# latch3.net
KiCad netlist of a schematic drawn in EAGLE
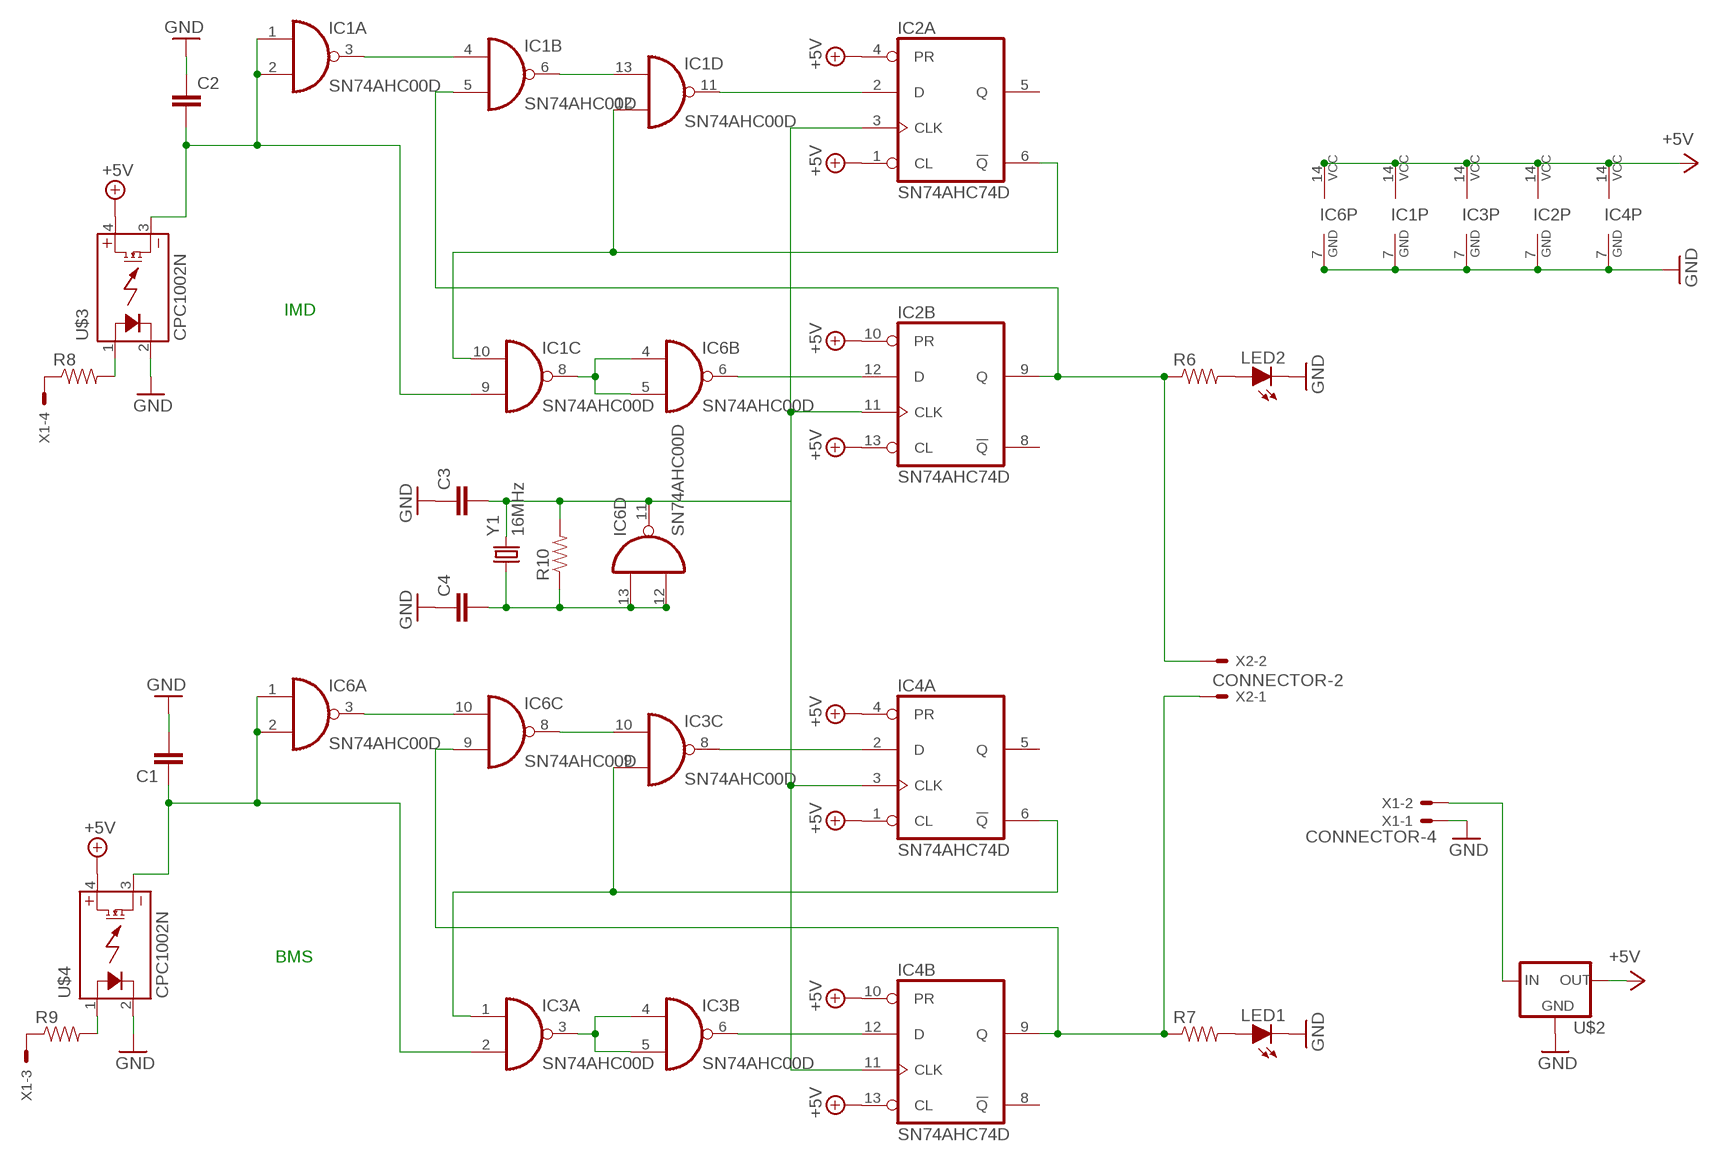
[diagram p0: schematic, sheet 1]

(export (version "E")
  (design (tool "Eeschema 10.0.6"))
  (components
    (comp (ref "C1")
      (value "CAP0402-CAP")
      (footprint "eagle-import:0402-CAP")
      (libsource (lib "eagle-import") (part "CAP0402-CAP"))
    )
    (comp (ref "C2")
      (value "CAP0402-CAP")
      (footprint "eagle-import:0402-CAP")
      (libsource (lib "eagle-import") (part "CAP0402-CAP"))
    )
    (comp (ref "C3")
      (value "CAP0402-CAP")
      (footprint "eagle-import:0402-CAP")
      (libsource (lib "eagle-import") (part "CAP0402-CAP"))
    )
    (comp (ref "C4")
      (value "CAP0402-CAP")
      (footprint "eagle-import:0402-CAP")
      (libsource (lib "eagle-import") (part "CAP0402-CAP"))
    )
    (comp (ref "IC1")
      (value "SN74AHC00D")
      (footprint "eagle-import:SOIC-14")
      (libsource (lib "eagle-import") (part "SN74AHC00D"))
    )
    (comp (ref "IC2")
      (value "SN74AHC74D")
      (footprint "eagle-import:SOIC-14")
      (libsource (lib "eagle-import") (part "SN74AHC74D"))
    )
    (comp (ref "IC3")
      (value "SN74AHC00D")
      (footprint "eagle-import:SOIC-14")
      (libsource (lib "eagle-import") (part "SN74AHC00D"))
    )
    (comp (ref "IC4")
      (value "SN74AHC74D")
      (footprint "eagle-import:SOIC-14")
      (libsource (lib "eagle-import") (part "SN74AHC74D"))
    )
    (comp (ref "IC6")
      (value "SN74AHC00D")
      (footprint "eagle-import:SOIC-14")
      (libsource (lib "eagle-import") (part "SN74AHC00D"))
    )
    (comp (ref "LED1")
      (value "LED-0805")
      (footprint "eagle-import:LED-805")
      (libsource (lib "eagle-import") (part "LED-0805"))
    )
    (comp (ref "LED2")
      (value "LED-0805")
      (footprint "eagle-import:LED-805")
      (libsource (lib "eagle-import") (part "LED-0805"))
    )
    (comp (ref "R6")
      (value "RESISTOR0402")
      (footprint "eagle-import:0402-RES")
      (libsource (lib "eagle-import") (part "RESISTOR0402"))
    )
    (comp (ref "R7")
      (value "RESISTOR0402")
      (footprint "eagle-import:0402-RES")
      (libsource (lib "eagle-import") (part "RESISTOR0402"))
    )
    (comp (ref "R8")
      (value "RESISTOR0402")
      (footprint "eagle-import:0402-RES")
      (libsource (lib "eagle-import") (part "RESISTOR0402"))
    )
    (comp (ref "R9")
      (value "RESISTOR0402")
      (footprint "eagle-import:0402-RES")
      (libsource (lib "eagle-import") (part "RESISTOR0402"))
    )
    (comp (ref "R10")
      (value "RESISTOR0402")
      (footprint "eagle-import:0402-RES")
      (libsource (lib "eagle-import") (part "RESISTOR0402"))
    )
    (comp (ref "U$2")
      (value "5VREG_LM340-NLM340MPX-5.0/NOPB")
      (footprint "eagle-import:SOT223")
      (libsource (lib "eagle-import") (part "5VREG_LM340-NLM340MPX-5.0/NOPB"))
    )
    (comp (ref "U$3")
      (value "CPC1002N")
      (footprint "eagle-import:SOP04")
      (libsource (lib "eagle-import") (part "CPC1002N"))
    )
    (comp (ref "U$4")
      (value "CPC1002N")
      (footprint "eagle-import:SOP04")
      (libsource (lib "eagle-import") (part "CPC1002N"))
    )
    (comp (ref "X1")
      (value "CONNECTOR-4")
      (footprint "eagle-import:MINIFIT_5566-4")
      (libsource (lib "eagle-import") (part "CONNECTOR-4"))
    )
    (comp (ref "X2")
      (value "CONNECTOR-2")
      (footprint "eagle-import:MINIFIT_5566-2")
      (libsource (lib "eagle-import") (part "CONNECTOR-2"))
    )
    (comp (ref "Y1")
      (value "16MHz")
      (footprint "eagle-import:CRYSTAL-SMD-3.2X1.5MM")
      (libsource (lib "eagle-import") (part "CRYSTAL3.2X1.5MM"))
    )
  )
  (nets
    (net (code "1") (name "+5V") (class "Default")
      (node (ref "IC1") (pin "14") (pinfunction "VCC_14") (pintype "power_in"))
      (node (ref "IC2") (pin "1") (pinfunction "CL_1") (pintype "input"))
      (node (ref "IC2") (pin "10") (pinfunction "PR_10") (pintype "input"))
      (node (ref "IC2") (pin "13") (pinfunction "CL_13") (pintype "input"))
      (node (ref "IC2") (pin "14") (pinfunction "VCC_14") (pintype "power_in"))
      (node (ref "IC2") (pin "4") (pinfunction "PR_4") (pintype "input"))
      (node (ref "IC3") (pin "14") (pinfunction "VCC_14") (pintype "power_in"))
      (node (ref "IC4") (pin "1") (pinfunction "CL_1") (pintype "input"))
      (node (ref "IC4") (pin "10") (pinfunction "PR_10") (pintype "input"))
      (node (ref "IC4") (pin "13") (pinfunction "CL_13") (pintype "input"))
      (node (ref "IC4") (pin "14") (pinfunction "VCC_14") (pintype "power_in"))
      (node (ref "IC4") (pin "4") (pinfunction "PR_4") (pintype "input"))
      (node (ref "IC6") (pin "14") (pinfunction "VCC_14") (pintype "power_in"))
      (node (ref "U$2") (pin "3") (pinfunction "OUT_3") (pintype "output"))
      (node (ref "U$3") (pin "4") (pinfunction "DC+_4") (pintype "passive"))
      (node (ref "U$4") (pin "4") (pinfunction "DC+_4") (pintype "passive"))
    )
    (net (code "2") (name "GND") (class "Default")
      (node (ref "C1") (pin "2") (pinfunction "2_2") (pintype "passive"))
      (node (ref "C2") (pin "1") (pinfunction "1_1") (pintype "passive"))
      (node (ref "C3") (pin "1") (pinfunction "1_1") (pintype "passive"))
      (node (ref "C4") (pin "1") (pinfunction "1_1") (pintype "passive"))
      (node (ref "IC1") (pin "7") (pinfunction "GND_7") (pintype "power_in"))
      (node (ref "IC2") (pin "7") (pinfunction "GND_7") (pintype "power_in"))
      (node (ref "IC3") (pin "7") (pinfunction "GND_7") (pintype "power_in"))
      (node (ref "IC4") (pin "7") (pinfunction "GND_7") (pintype "power_in"))
      (node (ref "IC6") (pin "7") (pinfunction "GND_7") (pintype "power_in"))
      (node (ref "LED1") (pin "C") (pinfunction "C_C") (pintype "passive"))
      (node (ref "LED2") (pin "C") (pinfunction "C_C") (pintype "passive"))
      (node (ref "U$2") (pin "2") (pinfunction "GND_2") (pintype "input"))
      (node (ref "U$2") (pin "4") (pinfunction "GND_4") (pintype "input"))
      (node (ref "U$3") (pin "2") (pinfunction "CONTROL-_2") (pintype "passive"))
      (node (ref "U$4") (pin "2") (pinfunction "CONTROL-_2") (pintype "passive"))
      (node (ref "X1") (pin "1") (pinfunction "S_1") (pintype "passive"))
    )
    (net (code "3") (name "Net-(IC1A-I0)") (class "Default")
      (node (ref "C2") (pin "2") (pinfunction "2_2") (pintype "passive"))
      (node (ref "IC1") (pin "1") (pinfunction "I0_1") (pintype "input"))
      (node (ref "IC1") (pin "2") (pinfunction "I1_2") (pintype "input"))
      (node (ref "IC1") (pin "9") (pinfunction "I1_9") (pintype "input"))
      (node (ref "U$3") (pin "3") (pinfunction "DC-_3") (pintype "passive"))
    )
    (net (code "4") (name "Net-(IC1A-O)") (class "Default")
      (node (ref "IC1") (pin "3") (pinfunction "O_3") (pintype "output"))
      (node (ref "IC1") (pin "4") (pinfunction "I0_4") (pintype "input"))
    )
    (net (code "5") (name "Net-(IC1B-I1)") (class "Default")
      (node (ref "IC1") (pin "5") (pinfunction "I1_5") (pintype "input"))
      (node (ref "IC2") (pin "9") (pinfunction "Q_9") (pintype "output"))
      (node (ref "R6") (pin "1") (pinfunction "1_1") (pintype "passive"))
      (node (ref "X2") (pin "2") (pinfunction "S_2") (pintype "passive"))
    )
    (net (code "6") (name "Net-(IC1B-O)") (class "Default")
      (node (ref "IC1") (pin "13") (pinfunction "I0_13") (pintype "input"))
      (node (ref "IC1") (pin "6") (pinfunction "O_6") (pintype "output"))
    )
    (net (code "7") (name "Net-(IC1C-I0)") (class "Default")
      (node (ref "IC1") (pin "10") (pinfunction "I0_10") (pintype "input"))
      (node (ref "IC1") (pin "12") (pinfunction "I1_12") (pintype "input"))
      (node (ref "IC2") (pin "6") (pinfunction "~{Q}_6") (pintype "output"))
    )
    (net (code "8") (name "Net-(IC1C-O)") (class "Default")
      (node (ref "IC1") (pin "8") (pinfunction "O_8") (pintype "output"))
      (node (ref "IC6") (pin "4") (pinfunction "I0_4") (pintype "input"))
      (node (ref "IC6") (pin "5") (pinfunction "I1_5") (pintype "input"))
    )
    (net (code "9") (name "Net-(IC1D-O)") (class "Default")
      (node (ref "IC1") (pin "11") (pinfunction "O_11") (pintype "output"))
      (node (ref "IC2") (pin "2") (pinfunction "D_2") (pintype "input"))
    )
    (net (code "10") (name "Net-(IC2A-CLK)") (class "Default")
      (node (ref "C3") (pin "2") (pinfunction "2_2") (pintype "passive"))
      (node (ref "IC2") (pin "11") (pinfunction "CLK_11") (pintype "input"))
      (node (ref "IC2") (pin "3") (pinfunction "CLK_3") (pintype "input"))
      (node (ref "IC4") (pin "11") (pinfunction "CLK_11") (pintype "input"))
      (node (ref "IC4") (pin "3") (pinfunction "CLK_3") (pintype "input"))
      (node (ref "IC6") (pin "11") (pinfunction "O_11") (pintype "output"))
      (node (ref "R10") (pin "2") (pinfunction "2_2") (pintype "passive"))
      (node (ref "Y1") (pin "P$2") (pinfunction "2_P$2") (pintype "passive"))
    )
    (net (code "11") (name "Net-(IC2B-D)") (class "Default")
      (node (ref "IC2") (pin "12") (pinfunction "D_12") (pintype "input"))
      (node (ref "IC6") (pin "6") (pinfunction "O_6") (pintype "output"))
    )
    (net (code "12") (name "Net-(IC3A-I0)") (class "Default")
      (node (ref "IC3") (pin "1") (pinfunction "I0_1") (pintype "input"))
      (node (ref "IC3") (pin "9") (pinfunction "I1_9") (pintype "input"))
      (node (ref "IC4") (pin "6") (pinfunction "~{Q}_6") (pintype "output"))
    )
    (net (code "13") (name "Net-(IC3A-I1)") (class "Default")
      (node (ref "C1") (pin "1") (pinfunction "1_1") (pintype "passive"))
      (node (ref "IC3") (pin "2") (pinfunction "I1_2") (pintype "input"))
      (node (ref "IC6") (pin "1") (pinfunction "I0_1") (pintype "input"))
      (node (ref "IC6") (pin "2") (pinfunction "I1_2") (pintype "input"))
      (node (ref "U$4") (pin "3") (pinfunction "DC-_3") (pintype "passive"))
    )
    (net (code "14") (name "Net-(IC3A-O)") (class "Default")
      (node (ref "IC3") (pin "3") (pinfunction "O_3") (pintype "output"))
      (node (ref "IC3") (pin "4") (pinfunction "I0_4") (pintype "input"))
      (node (ref "IC3") (pin "5") (pinfunction "I1_5") (pintype "input"))
    )
    (net (code "15") (name "Net-(IC3B-O)") (class "Default")
      (node (ref "IC3") (pin "6") (pinfunction "O_6") (pintype "output"))
      (node (ref "IC4") (pin "12") (pinfunction "D_12") (pintype "input"))
    )
    (net (code "16") (name "Net-(IC3C-I0)") (class "Default")
      (node (ref "IC3") (pin "10") (pinfunction "I0_10") (pintype "input"))
      (node (ref "IC6") (pin "8") (pinfunction "O_8") (pintype "output"))
    )
    (net (code "17") (name "Net-(IC3C-O)") (class "Default")
      (node (ref "IC3") (pin "8") (pinfunction "O_8") (pintype "output"))
      (node (ref "IC4") (pin "2") (pinfunction "D_2") (pintype "input"))
    )
    (net (code "18") (name "Net-(IC4B-Q)") (class "Default")
      (node (ref "IC4") (pin "9") (pinfunction "Q_9") (pintype "output"))
      (node (ref "IC6") (pin "9") (pinfunction "I1_9") (pintype "input"))
      (node (ref "R7") (pin "1") (pinfunction "1_1") (pintype "passive"))
      (node (ref "X2") (pin "1") (pinfunction "S_1") (pintype "passive"))
    )
    (net (code "19") (name "Net-(IC6A-O)") (class "Default")
      (node (ref "IC6") (pin "10") (pinfunction "I0_10") (pintype "input"))
      (node (ref "IC6") (pin "3") (pinfunction "O_3") (pintype "output"))
    )
    (net (code "20") (name "Net-(IC6D-I0)") (class "Default")
      (node (ref "C4") (pin "2") (pinfunction "2_2") (pintype "passive"))
      (node (ref "IC6") (pin "12") (pinfunction "I1_12") (pintype "input"))
      (node (ref "IC6") (pin "13") (pinfunction "I0_13") (pintype "input"))
      (node (ref "R10") (pin "1") (pinfunction "1_1") (pintype "passive"))
      (node (ref "Y1") (pin "P$1") (pinfunction "1_P$1") (pintype "passive"))
    )
    (net (code "21") (name "Net-(LED1-PadA)") (class "Default")
      (node (ref "LED1") (pin "A") (pinfunction "A_A") (pintype "passive"))
      (node (ref "R7") (pin "2") (pinfunction "2_2") (pintype "passive"))
    )
    (net (code "22") (name "Net-(LED2-PadA)") (class "Default")
      (node (ref "LED2") (pin "A") (pinfunction "A_A") (pintype "passive"))
      (node (ref "R6") (pin "2") (pinfunction "2_2") (pintype "passive"))
    )
    (net (code "23") (name "Net-(U$2-IN)") (class "Default")
      (node (ref "U$2") (pin "1") (pinfunction "IN_1") (pintype "input"))
      (node (ref "X1") (pin "2") (pinfunction "S_2") (pintype "passive"))
    )
    (net (code "24") (name "Net-(U$3-CONTROL+)") (class "Default")
      (node (ref "R8") (pin "2") (pinfunction "2_2") (pintype "passive"))
      (node (ref "U$3") (pin "1") (pinfunction "CONTROL+_1") (pintype "passive"))
    )
    (net (code "25") (name "Net-(U$4-CONTROL+)") (class "Default")
      (node (ref "R9") (pin "2") (pinfunction "2_2") (pintype "passive"))
      (node (ref "U$4") (pin "1") (pinfunction "CONTROL+_1") (pintype "passive"))
    )
    (net (code "26") (name "Net-(X1C-S)") (class "Default")
      (node (ref "R9") (pin "1") (pinfunction "1_1") (pintype "passive"))
      (node (ref "X1") (pin "3") (pinfunction "S_3") (pintype "passive"))
    )
    (net (code "27") (name "Net-(X1D-S)") (class "Default")
      (node (ref "R8") (pin "1") (pinfunction "1_1") (pintype "passive"))
      (node (ref "X1") (pin "4") (pinfunction "S_4") (pintype "passive"))
    )
    (net (code "28") (name "unconnected-(IC2A-Q-Pad5)") (class "Default")
      (node (ref "IC2") (pin "5") (pinfunction "Q_5") (pintype "output"))
    )
    (net (code "29") (name "unconnected-(IC2B-~{Q}-Pad8)") (class "Default")
      (node (ref "IC2") (pin "8") (pinfunction "~{Q}_8") (pintype "output"))
    )
    (net (code "30") (name "unconnected-(IC4A-Q-Pad5)") (class "Default")
      (node (ref "IC4") (pin "5") (pinfunction "Q_5") (pintype "output"))
    )
    (net (code "31") (name "unconnected-(IC4B-~{Q}-Pad8)") (class "Default")
      (node (ref "IC4") (pin "8") (pinfunction "~{Q}_8") (pintype "output"))
    )
  )
)
